# TP4056_PROTECTION_PCB.net
KiCad netlist of a schematic drawn in EAGLE
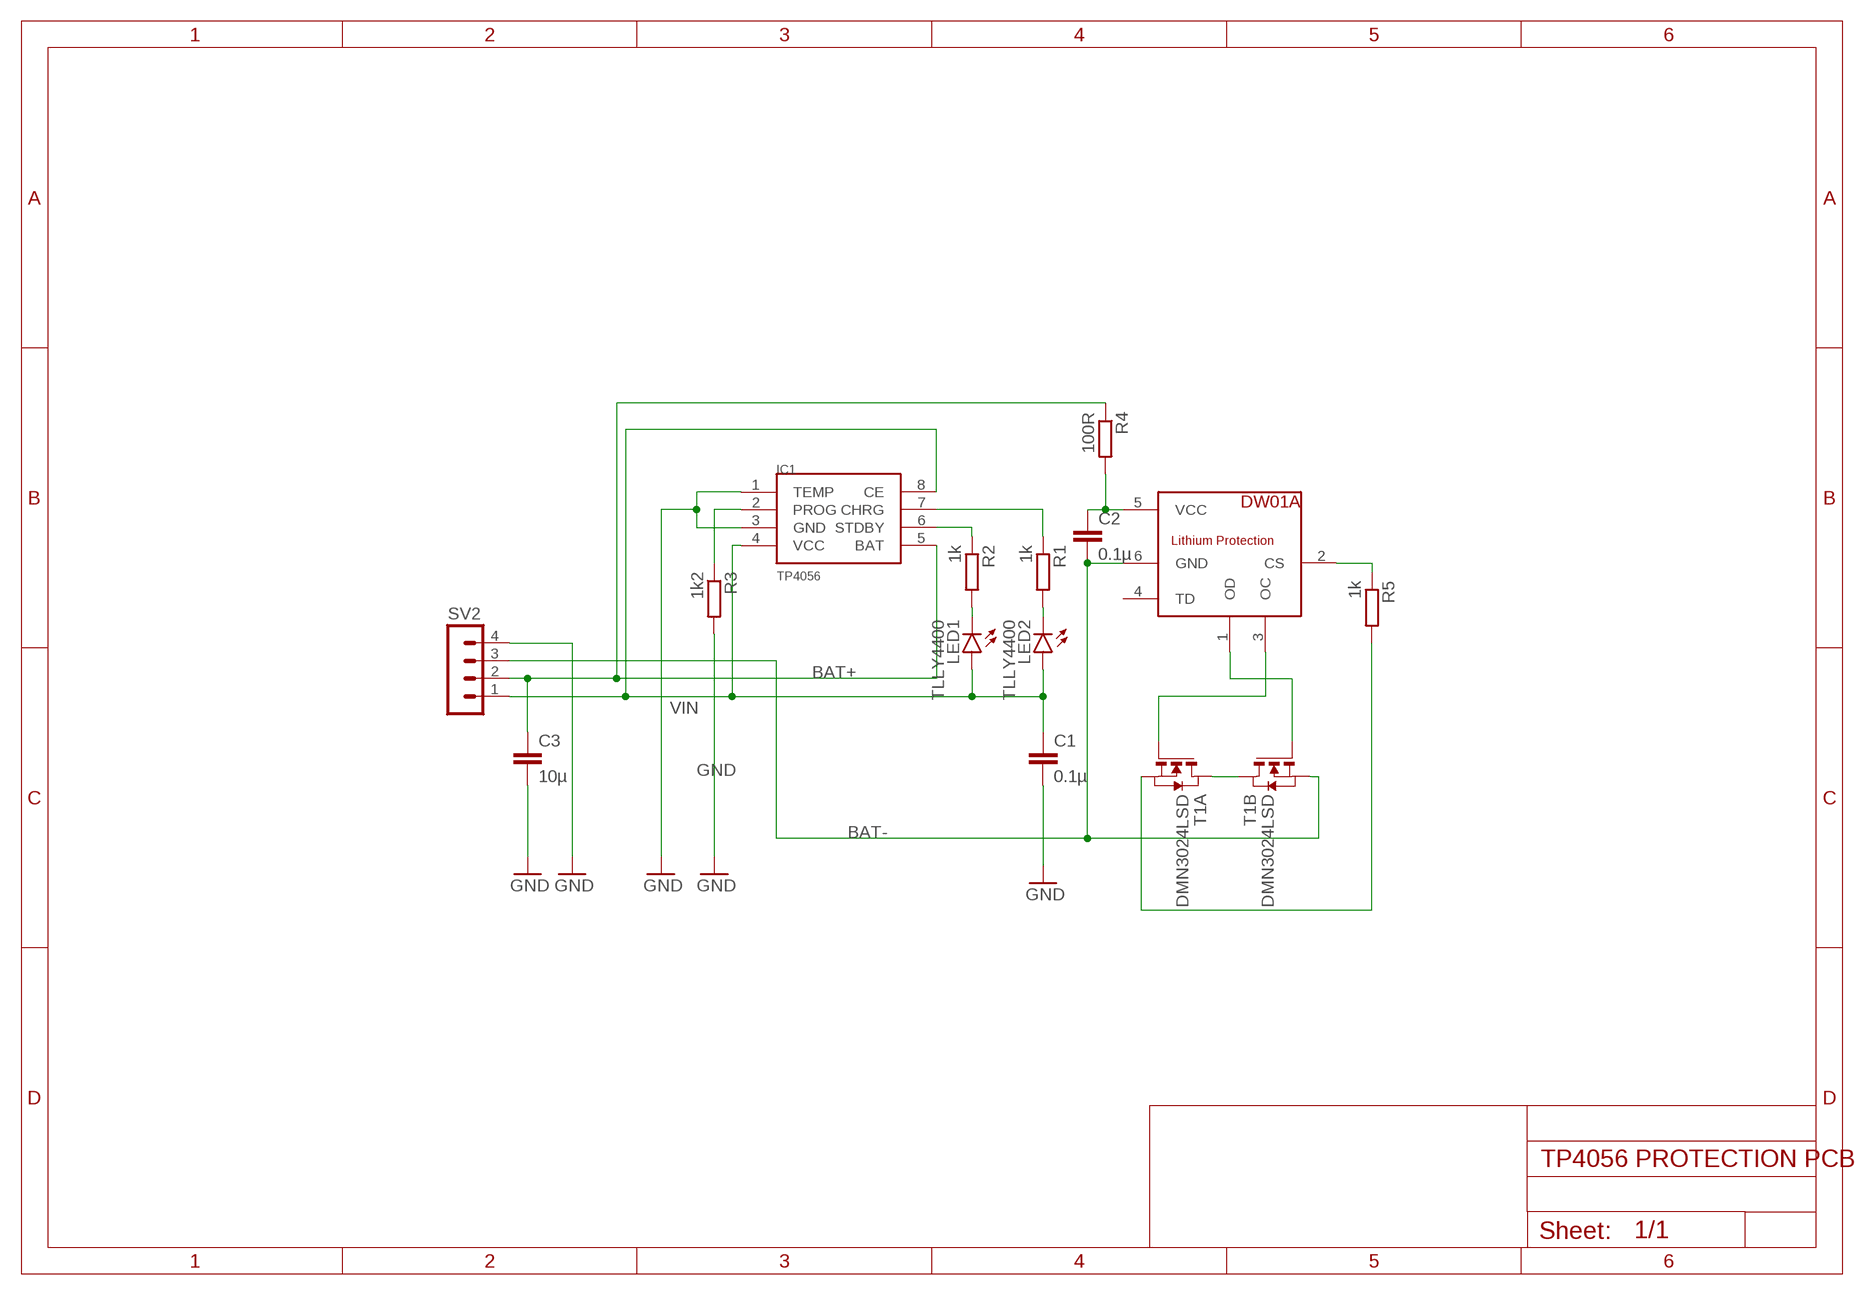
[diagram p0: schematic, sheet 1]

(export (version "E")
  (design (tool "Eeschema 10.0.6"))
  (components
    (comp (ref "C1")
      (value "0.1µ")
      (footprint "eagle-import:C1206")
      (libsource (lib "eagle-import") (part "C-EUC1206"))
    )
    (comp (ref "C2")
      (value "0.1µ")
      (footprint "eagle-import:C1206")
      (libsource (lib "eagle-import") (part "C-EUC1206"))
    )
    (comp (ref "C3")
      (value "10µ")
      (footprint "eagle-import:C1206")
      (libsource (lib "eagle-import") (part "C-EUC1206"))
    )
    (comp (ref "IC1")
      (value "TP4056")
      (footprint "eagle-import:SOP-8")
      (libsource (lib "eagle-import") (part "TP4056"))
    )
    (comp (ref "LED1")
      (value "TLLY4400")
      (footprint "eagle-import:LED3MM")
      (fields (field (name "MF") "VISHAY SEMICONDUCTOR"))
      (libsource (lib "eagle-import") (part "TLLY4400"))
    )
    (comp (ref "LED2")
      (value "TLLY4400")
      (footprint "eagle-import:LED3MM")
      (fields (field (name "MF") "VISHAY SEMICONDUCTOR"))
      (libsource (lib "eagle-import") (part "TLLY4400"))
    )
    (comp (ref "R1")
      (value "1k")
      (footprint "eagle-import:R1206W")
      (libsource (lib "eagle-import") (part "R-EU_R1206W"))
    )
    (comp (ref "R2")
      (value "1k")
      (footprint "eagle-import:R1206W")
      (libsource (lib "eagle-import") (part "R-EU_R1206W"))
    )
    (comp (ref "R3")
      (value "1k2")
      (footprint "eagle-import:R1206W")
      (libsource (lib "eagle-import") (part "R-EU_R1206W"))
    )
    (comp (ref "R4")
      (value "100R")
      (footprint "eagle-import:R1206W")
      (libsource (lib "eagle-import") (part "R-EU_R1206W"))
    )
    (comp (ref "R5")
      (value "1k")
      (footprint "eagle-import:R1206W")
      (libsource (lib "eagle-import") (part "R-EU_R1206W"))
    )
    (comp (ref "SV2")
      (value "MA04-1")
      (footprint "eagle-import:MA04-1")
      (libsource (lib "eagle-import") (part "MA04-1"))
    )
    (comp (ref "T1")
      (value "DMN3024LSD")
      (footprint "eagle-import:TSSOP-8")
      (libsource (lib "eagle-import") (part "DMN3024LSD"))
    )
    (comp (ref "U$1")
      (value "DW01A")
      (footprint "eagle-import:SOT23-6")
      (libsource (lib "eagle-import") (part "DW01A"))
    )
  )
  (nets
    (net (code "1") (name "/BAT+") (class "Default")
      (node (ref "C3") (pin "1") (pinfunction "1_1") (pintype "passive"))
      (node (ref "IC1") (pin "5") (pinfunction "BAT_5") (pintype "bidirectional"))
      (node (ref "R4") (pin "1") (pinfunction "1_1") (pintype "passive"))
      (node (ref "SV2") (pin "2") (pinfunction "2_2") (pintype "passive"))
    )
    (net (code "2") (name "/BAT-") (class "Default")
      (node (ref "C2") (pin "2") (pinfunction "2_2") (pintype "passive"))
      (node (ref "SV2") (pin "3") (pinfunction "3_3") (pintype "passive"))
      (node (ref "T1") (pin "6") (pinfunction "S_6") (pintype "passive"))
      (node (ref "T1") (pin "7") (pinfunction "S_7") (pintype "passive"))
      (node (ref "U$1") (pin "6") (pinfunction "GND_6") (pintype "bidirectional"))
    )
    (net (code "3") (name "/VIN") (class "Default")
      (node (ref "C1") (pin "1") (pinfunction "1_1") (pintype "passive"))
      (node (ref "IC1") (pin "4") (pinfunction "VCC_4") (pintype "bidirectional"))
      (node (ref "IC1") (pin "8") (pinfunction "CE_8") (pintype "bidirectional"))
      (node (ref "LED1") (pin "A") (pinfunction "A_A") (pintype "passive"))
      (node (ref "LED2") (pin "A") (pinfunction "A_A") (pintype "passive"))
      (node (ref "SV2") (pin "1") (pinfunction "1_1") (pintype "passive"))
    )
    (net (code "4") (name "GND") (class "Default")
      (node (ref "C1") (pin "2") (pinfunction "2_2") (pintype "passive"))
      (node (ref "C3") (pin "2") (pinfunction "2_2") (pintype "passive"))
      (node (ref "IC1") (pin "1") (pinfunction "TEMP_1") (pintype "bidirectional"))
      (node (ref "IC1") (pin "3") (pinfunction "GND_3") (pintype "bidirectional"))
      (node (ref "R3") (pin "2") (pinfunction "2_2") (pintype "passive"))
      (node (ref "SV2") (pin "4") (pinfunction "4_4") (pintype "passive"))
    )
    (net (code "5") (name "Net-(IC1-CHRG)") (class "Default")
      (node (ref "IC1") (pin "7") (pinfunction "CHRG_7") (pintype "bidirectional"))
      (node (ref "R1") (pin "1") (pinfunction "1_1") (pintype "passive"))
    )
    (net (code "6") (name "Net-(IC1-PROG)") (class "Default")
      (node (ref "IC1") (pin "2") (pinfunction "PROG_2") (pintype "bidirectional"))
      (node (ref "R3") (pin "1") (pinfunction "1_1") (pintype "passive"))
    )
    (net (code "7") (name "Net-(IC1-STDBY)") (class "Default")
      (node (ref "IC1") (pin "6") (pinfunction "STDBY_6") (pintype "bidirectional"))
      (node (ref "R2") (pin "1") (pinfunction "1_1") (pintype "passive"))
    )
    (net (code "8") (name "Net-(LED1-C)") (class "Default")
      (node (ref "LED1") (pin "K") (pinfunction "C_K") (pintype "passive"))
      (node (ref "R2") (pin "2") (pinfunction "2_2") (pintype "passive"))
    )
    (net (code "9") (name "Net-(LED2-C)") (class "Default")
      (node (ref "LED2") (pin "K") (pinfunction "C_K") (pintype "passive"))
      (node (ref "R1") (pin "2") (pinfunction "2_2") (pintype "passive"))
    )
    (net (code "10") (name "Net-(R5-Pad2)") (class "Default")
      (node (ref "R5") (pin "2") (pinfunction "2_2") (pintype "passive"))
      (node (ref "T1") (pin "2") (pinfunction "S_2") (pintype "passive"))
      (node (ref "T1") (pin "3") (pinfunction "S_3") (pintype "passive"))
    )
    (net (code "11") (name "Net-(T1A-D)") (class "Default")
      (node (ref "T1") (pin "1") (pinfunction "D_1") (pintype "passive"))
      (node (ref "T1") (pin "8") (pinfunction "D_8") (pintype "passive"))
    )
    (net (code "12") (name "Net-(T1A-G)") (class "Default")
      (node (ref "T1") (pin "4") (pinfunction "G_4") (pintype "passive"))
      (node (ref "U$1") (pin "3") (pinfunction "OC_3") (pintype "bidirectional"))
    )
    (net (code "13") (name "Net-(T1B-G)") (class "Default")
      (node (ref "T1") (pin "5") (pinfunction "G_5") (pintype "passive"))
      (node (ref "U$1") (pin "1") (pinfunction "OD_1") (pintype "bidirectional"))
    )
    (net (code "14") (name "Net-(U$1-CS)") (class "Default")
      (node (ref "R5") (pin "1") (pinfunction "1_1") (pintype "passive"))
      (node (ref "U$1") (pin "2") (pinfunction "CS_2") (pintype "bidirectional"))
    )
    (net (code "15") (name "Net-(U$1-VCC)") (class "Default")
      (node (ref "C2") (pin "1") (pinfunction "1_1") (pintype "passive"))
      (node (ref "R4") (pin "2") (pinfunction "2_2") (pintype "passive"))
      (node (ref "U$1") (pin "5") (pinfunction "VCC_5") (pintype "bidirectional"))
    )
    (net (code "16") (name "unconnected-(U$1-TD-Pad4)") (class "Default")
      (node (ref "U$1") (pin "4") (pinfunction "TD_4") (pintype "bidirectional"))
    )
  )
)
